# Receptor_D.net
KiCad netlist of a schematic drawn in Altium Designer
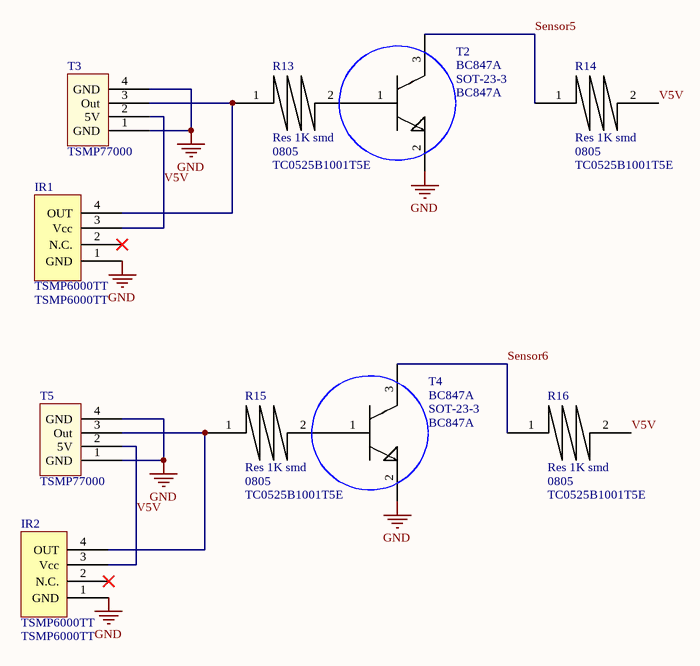
[diagram p0: Receptor D.SchDoc]

(export (version "E")
  (design (tool "Eeschema 10.0.6"))
  (components
    (comp (ref "IR1")
      (value "TSMP6000TT")
      (footprint "TSMP6000TT")
      (fields (field (name "PART") "TSMP6000TT"))
      (libsource (lib "Integrated_Library") (part "TSMP6000TT"))
    )
    (comp (ref "IR2")
      (value "TSMP6000TT")
      (footprint "TSMP6000TT")
      (fields (field (name "PART") "TSMP6000TT"))
      (libsource (lib "Integrated_Library") (part "TSMP6000TT"))
    )
    (comp (ref "R13")
      (value "Res 1K smd")
      (footprint "RES 1K")
      (fields (field (name "PACKAGE") "0805") (field (name "MFR.PART #") "TC0525B1001T5E"))
      (libsource (lib "Integrated_Library") (part "Res 1K smd"))
    )
    (comp (ref "R14")
      (value "Res 1K smd")
      (footprint "RES 1K")
      (fields (field (name "PACKAGE") "0805") (field (name "MFR.PART #") "TC0525B1001T5E"))
      (libsource (lib "Integrated_Library") (part "Res 1K smd"))
    )
    (comp (ref "R15")
      (value "Res 1K smd")
      (footprint "RES 1K")
      (fields (field (name "PACKAGE") "0805") (field (name "MFR.PART #") "TC0525B1001T5E"))
      (libsource (lib "Integrated_Library") (part "Res 1K smd"))
    )
    (comp (ref "R16")
      (value "Res 1K smd")
      (footprint "RES 1K")
      (fields (field (name "PACKAGE") "0805") (field (name "MFR.PART #") "TC0525B1001T5E"))
      (libsource (lib "Integrated_Library") (part "Res 1K smd"))
    )
    (comp (ref "T2")
      (value "BC847A")
      (footprint "BC847A")
      (fields (field (name "PACKAGE") "SOT-23-3") (field (name "MFR.PART #") "BC847A"))
      (libsource (lib "Integrated_Library") (part "BC847A"))
    )
    (comp (ref "T3")
      (value "TSMP77000")
      (footprint "TSMP77000")
      (libsource (lib "Integrated_Library") (part "TSMP77000"))
    )
    (comp (ref "T4")
      (value "BC847A")
      (footprint "BC847A")
      (fields (field (name "PACKAGE") "SOT-23-3") (field (name "MFR.PART #") "BC847A"))
      (libsource (lib "Integrated_Library") (part "BC847A"))
    )
    (comp (ref "T5")
      (value "TSMP77000")
      (footprint "TSMP77000")
      (libsource (lib "Integrated_Library") (part "TSMP77000"))
    )
  )
  (nets
    (net (code "1") (name "/Sensor5") (class "Default")
      (node (ref "R14") (pin "1") (pinfunction "1_1") (pintype "passive"))
      (node (ref "T2") (pin "3") (pinfunction "3_3") (pintype "passive"))
    )
    (net (code "2") (name "/Sensor6") (class "Default")
      (node (ref "R16") (pin "1") (pinfunction "1_1") (pintype "passive"))
      (node (ref "T4") (pin "3") (pinfunction "3_3") (pintype "passive"))
    )
    (net (code "3") (name "/V5V") (class "Default")
      (node (ref "IR1") (pin "3") (pinfunction "Vcc_3") (pintype "passive"))
      (node (ref "IR2") (pin "3") (pinfunction "Vcc_3") (pintype "passive"))
      (node (ref "R14") (pin "2") (pinfunction "2_2") (pintype "passive"))
      (node (ref "R16") (pin "2") (pinfunction "2_2") (pintype "passive"))
      (node (ref "T3") (pin "2") (pinfunction "5V_2") (pintype "passive"))
      (node (ref "T5") (pin "2") (pinfunction "5V_2") (pintype "passive"))
    )
    (net (code "4") (name "GND") (class "Default")
      (node (ref "IR1") (pin "1") (pinfunction "GND_1") (pintype "passive"))
      (node (ref "IR2") (pin "1") (pinfunction "GND_1") (pintype "passive"))
      (node (ref "T2") (pin "2") (pinfunction "2_2") (pintype "passive"))
      (node (ref "T3") (pin "1") (pinfunction "GND_1") (pintype "passive"))
      (node (ref "T3") (pin "4") (pinfunction "GND_4") (pintype "passive"))
      (node (ref "T4") (pin "2") (pinfunction "2_2") (pintype "passive"))
      (node (ref "T5") (pin "1") (pinfunction "GND_1") (pintype "passive"))
      (node (ref "T5") (pin "4") (pinfunction "GND_4") (pintype "passive"))
    )
    (net (code "5") (name "Net-(IR1-OUT)") (class "Default")
      (node (ref "IR1") (pin "4") (pinfunction "OUT_4") (pintype "passive"))
      (node (ref "R13") (pin "1") (pinfunction "1_1") (pintype "passive"))
      (node (ref "T3") (pin "3") (pinfunction "Out_3") (pintype "passive"))
    )
    (net (code "6") (name "Net-(IR2-OUT)") (class "Default")
      (node (ref "IR2") (pin "4") (pinfunction "OUT_4") (pintype "passive"))
      (node (ref "R15") (pin "1") (pinfunction "1_1") (pintype "passive"))
      (node (ref "T5") (pin "3") (pinfunction "Out_3") (pintype "passive"))
    )
    (net (code "7") (name "Net-(R13-Pad2)") (class "Default")
      (node (ref "R13") (pin "2") (pinfunction "2_2") (pintype "passive"))
      (node (ref "T2") (pin "1") (pinfunction "1_1") (pintype "passive"))
    )
    (net (code "8") (name "Net-(R15-Pad2)") (class "Default")
      (node (ref "R15") (pin "2") (pinfunction "2_2") (pintype "passive"))
      (node (ref "T4") (pin "1") (pinfunction "1_1") (pintype "passive"))
    )
    (net (code "9") (name "unconnected-(IR1-N.C.-Pad2)") (class "Default")
      (node (ref "IR1") (pin "2") (pinfunction "N.C._2") (pintype "passive+no_connect"))
    )
    (net (code "10") (name "unconnected-(IR2-N.C.-Pad2)") (class "Default")
      (node (ref "IR2") (pin "2") (pinfunction "N.C._2") (pintype "passive+no_connect"))
    )
  )
)
